# sonic_screwdriver.net
KiCad netlist of a schematic drawn in EAGLE
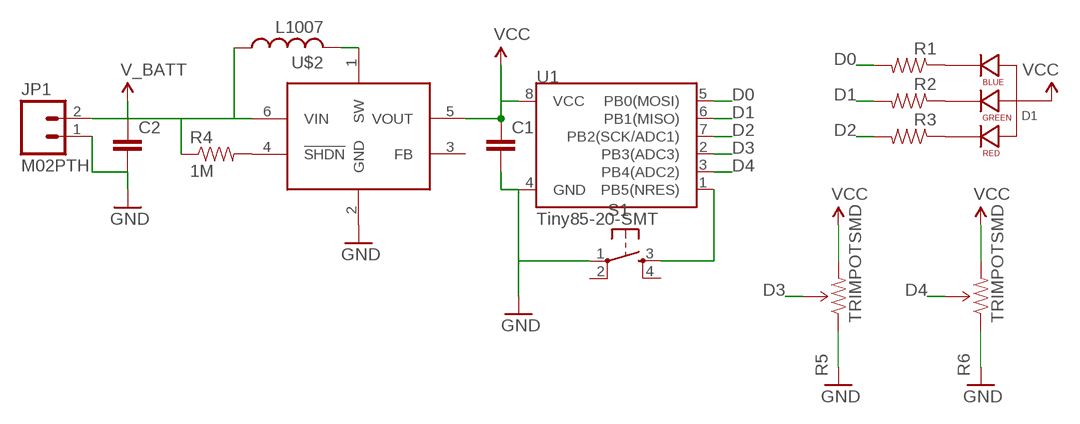
[diagram p0: schematic, sheet 1]

(export (version "E")
  (design (tool "Eeschema 10.0.6"))
  (components
    (comp (ref "C1")
      (value "CAP1206")
      (footprint "eagle-import:1206")
      (libsource (lib "eagle-import") (part "CAP1206"))
    )
    (comp (ref "C2")
      (value "CAP1206")
      (footprint "eagle-import:1206")
      (libsource (lib "eagle-import") (part "CAP1206"))
    )
    (comp (ref "D1")
      (value "LED-RGB-CA-THRUEDGE")
      (footprint "eagle-import:LED-RGB-EDGE")
      (libsource (lib "eagle-import") (part "LED-RGB-CA-THRUEDGE"))
    )
    (comp (ref "JP1")
      (value "M02PTH")
      (footprint "eagle-import:1X02")
      (libsource (lib "eagle-import") (part "M02PTH"))
    )
    (comp (ref "R1")
      (value "RESISTOR0805-RES")
      (footprint "eagle-import:0805")
      (libsource (lib "eagle-import") (part "RESISTOR0805-RES"))
    )
    (comp (ref "R2")
      (value "RESISTOR0805-RES")
      (footprint "eagle-import:0805")
      (libsource (lib "eagle-import") (part "RESISTOR0805-RES"))
    )
    (comp (ref "R3")
      (value "RESISTOR0805-RES")
      (footprint "eagle-import:0805")
      (libsource (lib "eagle-import") (part "RESISTOR0805-RES"))
    )
    (comp (ref "R4")
      (value "1M")
      (footprint "eagle-import:0805")
      (libsource (lib "eagle-import") (part "RESISTOR0805-RES"))
    )
    (comp (ref "R5")
      (value "TRIMPOTSMD")
      (footprint "eagle-import:TRIMPOT-3MM")
      (libsource (lib "eagle-import") (part "TRIMPOTSMD"))
    )
    (comp (ref "R6")
      (value "TRIMPOTSMD")
      (footprint "eagle-import:TRIMPOT-3MM")
      (libsource (lib "eagle-import") (part "TRIMPOTSMD"))
    )
    (comp (ref "S1")
      (value "TAC_SWITCHSMD")
      (footprint "eagle-import:TACTILE-SWITCH-SMD")
      (libsource (lib "eagle-import") (part "TAC_SWITCHSMD"))
    )
    (comp (ref "U$1")
      (value "AAT1217")
      (footprint "eagle-import:TSOT-23-6")
      (libsource (lib "eagle-import") (part "AAT1217"))
    )
    (comp (ref "U$2")
      (value "L1007")
      (footprint "eagle-import:L1007")
      (libsource (lib "eagle-import") (part "L1007"))
    )
    (comp (ref "U1")
      (value "Tiny85-20-SMT")
      (footprint "eagle-import:SO08-EIAJ")
      (libsource (lib "eagle-import") (part "ATTINY45TINY85-20-SMT"))
    )
  )
  (nets
    (net (code "1") (name "/D0") (class "Default")
      (node (ref "R1") (pin "2") (pinfunction "2_2") (pintype "passive"))
      (node (ref "U1") (pin "5") (pinfunction "PB0(MOSI)_5") (pintype "bidirectional"))
    )
    (net (code "2") (name "/D1") (class "Default")
      (node (ref "R2") (pin "2") (pinfunction "2_2") (pintype "passive"))
      (node (ref "U1") (pin "6") (pinfunction "PB1(MISO)_6") (pintype "bidirectional"))
    )
    (net (code "3") (name "/D2") (class "Default")
      (node (ref "R3") (pin "2") (pinfunction "2_2") (pintype "passive"))
      (node (ref "U1") (pin "7") (pinfunction "PB2(SCK/ADC1)_7") (pintype "bidirectional"))
    )
    (net (code "4") (name "/D3") (class "Default")
      (node (ref "R5") (pin "2") (pinfunction "WIPER_2") (pintype "passive"))
      (node (ref "U1") (pin "2") (pinfunction "PB3(ADC3)_2") (pintype "bidirectional"))
    )
    (net (code "5") (name "/D4") (class "Default")
      (node (ref "R6") (pin "2") (pinfunction "WIPER_2") (pintype "passive"))
      (node (ref "U1") (pin "3") (pinfunction "PB4(ADC2)_3") (pintype "bidirectional"))
    )
    (net (code "6") (name "GND") (class "Default")
      (node (ref "C1") (pin "2") (pinfunction "2_2") (pintype "passive"))
      (node (ref "C2") (pin "2") (pinfunction "2_2") (pintype "passive"))
      (node (ref "JP1") (pin "1") (pinfunction "1_1") (pintype "passive"))
      (node (ref "R5") (pin "1") (pinfunction "CCW_1") (pintype "passive"))
      (node (ref "R6") (pin "1") (pinfunction "CCW_1") (pintype "passive"))
      (node (ref "S1") (pin "1") (pinfunction "1_1") (pintype "passive"))
      (node (ref "U$1") (pin "2") (pinfunction "GND_2") (pintype "bidirectional"))
      (node (ref "U1") (pin "4") (pinfunction "GND_4") (pintype "bidirectional"))
    )
    (net (code "7") (name "Net-(D1-BLUE_CATHODE)") (class "Default")
      (node (ref "D1") (pin "4") (pinfunction "BLUE_CATHODE_4") (pintype "bidirectional"))
      (node (ref "R1") (pin "1") (pinfunction "1_1") (pintype "passive"))
    )
    (net (code "8") (name "Net-(D1-GREEN_CATHODE)") (class "Default")
      (node (ref "D1") (pin "3") (pinfunction "GREEN_CATHODE_3") (pintype "bidirectional"))
      (node (ref "R2") (pin "1") (pinfunction "1_1") (pintype "passive"))
    )
    (net (code "9") (name "Net-(D1-RED_CATHODE)") (class "Default")
      (node (ref "D1") (pin "1") (pinfunction "RED_CATHODE_1") (pintype "bidirectional"))
      (node (ref "R3") (pin "1") (pinfunction "1_1") (pintype "passive"))
    )
    (net (code "10") (name "Net-(U$1-SW)") (class "Default")
      (node (ref "U$1") (pin "1") (pinfunction "SW_1") (pintype "bidirectional"))
      (node (ref "U$2") (pin "P$2") (pinfunction "2_P$2") (pintype "passive"))
    )
    (net (code "11") (name "Net-(U$1-~{SHDN})") (class "Default")
      (node (ref "R4") (pin "2") (pinfunction "2_2") (pintype "passive"))
      (node (ref "U$1") (pin "4") (pinfunction "~{SHDN}_4") (pintype "bidirectional"))
    )
    (net (code "12") (name "Net-(U1-PB5(NRES))") (class "Default")
      (node (ref "S1") (pin "3") (pinfunction "3_3") (pintype "passive"))
      (node (ref "U1") (pin "1") (pinfunction "PB5(NRES)_1") (pintype "bidirectional"))
    )
    (net (code "13") (name "VCC") (class "Default")
      (node (ref "C1") (pin "1") (pinfunction "1_1") (pintype "passive"))
      (node (ref "D1") (pin "2") (pinfunction "ANODE_2") (pintype "bidirectional"))
      (node (ref "R5") (pin "3") (pinfunction "CW_3") (pintype "passive"))
      (node (ref "R6") (pin "3") (pinfunction "CW_3") (pintype "passive"))
      (node (ref "U$1") (pin "5") (pinfunction "VOUT_5") (pintype "bidirectional"))
      (node (ref "U1") (pin "8") (pinfunction "VCC_8") (pintype "bidirectional"))
    )
    (net (code "14") (name "V_BATT") (class "Default")
      (node (ref "C2") (pin "1") (pinfunction "1_1") (pintype "passive"))
      (node (ref "JP1") (pin "2") (pinfunction "2_2") (pintype "passive"))
      (node (ref "R4") (pin "1") (pinfunction "1_1") (pintype "passive"))
      (node (ref "U$1") (pin "6") (pinfunction "VIN_6") (pintype "bidirectional"))
      (node (ref "U$2") (pin "P$1") (pinfunction "1_P$1") (pintype "passive"))
    )
    (net (code "15") (name "unconnected-(S1-Pad2)") (class "Default")
      (node (ref "S1") (pin "2") (pinfunction "2_2") (pintype "passive"))
    )
    (net (code "16") (name "unconnected-(S1-Pad4)") (class "Default")
      (node (ref "S1") (pin "4") (pinfunction "4_4") (pintype "passive"))
    )
    (net (code "17") (name "unconnected-(U$1-FB-Pad3)") (class "Default")
      (node (ref "U$1") (pin "3") (pinfunction "FB_3") (pintype "bidirectional"))
    )
  )
)
